# untitled.net
KiCad netlist of a schematic drawn in EAGLE
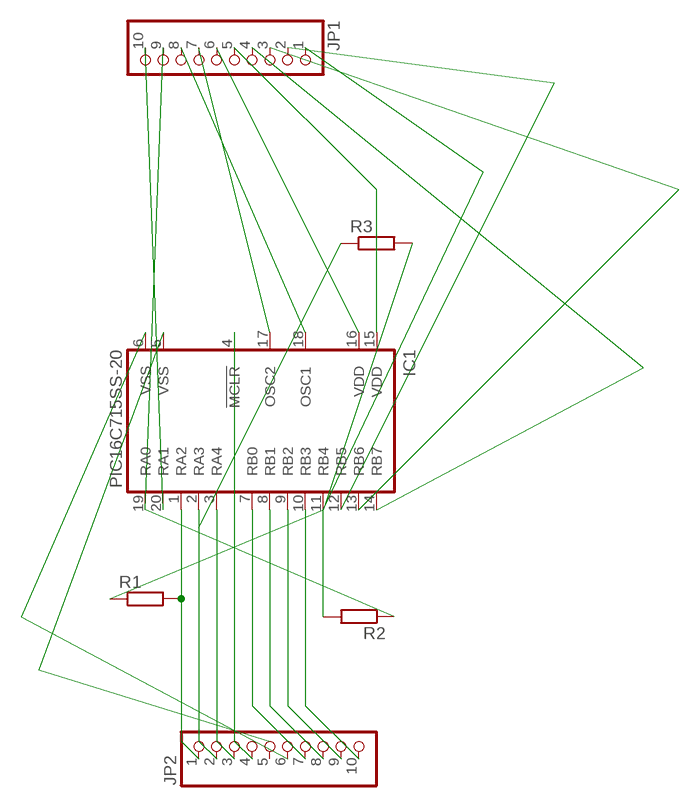
[diagram p0: schematic, sheet 1]

(export (version "E")
  (design (tool "Eeschema 10.0.6"))
  (components
    (comp (ref "IC1")
      (value "PIC16C715SS-20")
      (footprint "eagle-import:SSOP20")
      (fields (field (name "MF") "MICROCHIP") (field (name "MPN") "PIC16C715-04/SS"))
      (libsource (lib "eagle-import") (part "PIC16C?-20SS715"))
    )
    (comp (ref "JP1")
      (value "PINHD-1X10")
      (footprint "eagle-import:1X10")
      (libsource (lib "eagle-import") (part "PINHD-1X10"))
    )
    (comp (ref "JP2")
      (value "PINHD-1X10")
      (footprint "eagle-import:1X10")
      (libsource (lib "eagle-import") (part "PINHD-1X10"))
    )
    (comp (ref "R1")
      (value "R-EU_0207/10")
      (footprint "eagle-import:0207_10")
      (libsource (lib "eagle-import") (part "R-EU_0207/10"))
    )
    (comp (ref "R2")
      (value "R-EU_0204/2V")
      (footprint "eagle-import:0204V")
      (libsource (lib "eagle-import") (part "R-EU_0204/2V"))
    )
    (comp (ref "R3")
      (value "R-EU_0204/2V")
      (footprint "eagle-import:0204V")
      (libsource (lib "eagle-import") (part "R-EU_0204/2V"))
    )
  )
  (nets
    (net (code "1") (name "Net-(IC1-OSC1)") (class "Default")
      (node (ref "IC1") (pin "18") (pinfunction "OSC1_18") (pintype "input"))
      (node (ref "JP1") (pin "8") (pinfunction "8_8") (pintype "passive"))
    )
    (net (code "2") (name "Net-(IC1-OSC2)") (class "Default")
      (node (ref "IC1") (pin "17") (pinfunction "OSC2_17") (pintype "output"))
      (node (ref "JP1") (pin "7") (pinfunction "7_7") (pintype "passive"))
    )
    (net (code "3") (name "Net-(IC1-RA0)") (class "Default")
      (node (ref "IC1") (pin "19") (pinfunction "RA0_19") (pintype "bidirectional"))
      (node (ref "JP1") (pin "9") (pinfunction "9_9") (pintype "passive"))
      (node (ref "R2") (pin "1") (pinfunction "1_1") (pintype "passive"))
    )
    (net (code "4") (name "Net-(IC1-RA1)") (class "Default")
      (node (ref "IC1") (pin "20") (pinfunction "RA1_20") (pintype "bidirectional"))
      (node (ref "JP1") (pin "10") (pinfunction "10_10") (pintype "passive"))
    )
    (net (code "5") (name "Net-(IC1-RA2)") (class "Default")
      (node (ref "IC1") (pin "1") (pinfunction "RA2_1") (pintype "bidirectional"))
      (node (ref "JP2") (pin "1") (pinfunction "1_1") (pintype "passive"))
      (node (ref "R1") (pin "2") (pinfunction "2_2") (pintype "passive"))
    )
    (net (code "6") (name "Net-(IC1-RA3)") (class "Default")
      (node (ref "IC1") (pin "2") (pinfunction "RA3_2") (pintype "bidirectional"))
      (node (ref "JP2") (pin "2") (pinfunction "2_2") (pintype "passive"))
      (node (ref "R3") (pin "1") (pinfunction "1_1") (pintype "passive"))
    )
    (net (code "7") (name "Net-(IC1-RA4)") (class "Default")
      (node (ref "IC1") (pin "3") (pinfunction "RA4_3") (pintype "bidirectional"))
      (node (ref "JP2") (pin "3") (pinfunction "3_3") (pintype "passive"))
    )
    (net (code "8") (name "Net-(IC1-RB0)") (class "Default")
      (node (ref "IC1") (pin "7") (pinfunction "RB0_7") (pintype "bidirectional"))
      (node (ref "JP2") (pin "7") (pinfunction "7_7") (pintype "passive"))
    )
    (net (code "9") (name "Net-(IC1-RB1)") (class "Default")
      (node (ref "IC1") (pin "8") (pinfunction "RB1_8") (pintype "bidirectional"))
      (node (ref "JP2") (pin "8") (pinfunction "8_8") (pintype "passive"))
    )
    (net (code "10") (name "Net-(IC1-RB2)") (class "Default")
      (node (ref "IC1") (pin "9") (pinfunction "RB2_9") (pintype "bidirectional"))
      (node (ref "JP2") (pin "9") (pinfunction "9_9") (pintype "passive"))
    )
    (net (code "11") (name "Net-(IC1-RB3)") (class "Default")
      (node (ref "IC1") (pin "10") (pinfunction "RB3_10") (pintype "bidirectional"))
      (node (ref "JP2") (pin "10") (pinfunction "10_10") (pintype "passive"))
    )
    (net (code "12") (name "Net-(IC1-RB4)") (class "Default")
      (node (ref "IC1") (pin "11") (pinfunction "RB4_11") (pintype "bidirectional"))
      (node (ref "JP1") (pin "1") (pinfunction "1_1") (pintype "passive"))
      (node (ref "R1") (pin "1") (pinfunction "1_1") (pintype "passive"))
      (node (ref "R2") (pin "2") (pinfunction "2_2") (pintype "passive"))
      (node (ref "R3") (pin "2") (pinfunction "2_2") (pintype "passive"))
    )
    (net (code "13") (name "Net-(IC1-RB5)") (class "Default")
      (node (ref "IC1") (pin "12") (pinfunction "RB5_12") (pintype "bidirectional"))
      (node (ref "JP1") (pin "2") (pinfunction "2_2") (pintype "passive"))
    )
    (net (code "14") (name "Net-(IC1-RB6)") (class "Default")
      (node (ref "IC1") (pin "13") (pinfunction "RB6_13") (pintype "bidirectional"))
      (node (ref "JP1") (pin "3") (pinfunction "3_3") (pintype "passive"))
    )
    (net (code "15") (name "Net-(IC1-RB7)") (class "Default")
      (node (ref "IC1") (pin "14") (pinfunction "RB7_14") (pintype "bidirectional"))
      (node (ref "JP1") (pin "4") (pinfunction "4_4") (pintype "passive"))
    )
    (net (code "16") (name "Net-(IC1-VDD-Pad15)") (class "Default")
      (node (ref "IC1") (pin "15") (pinfunction "VDD_15") (pintype "power_in"))
      (node (ref "JP1") (pin "5") (pinfunction "5_5") (pintype "passive"))
    )
    (net (code "17") (name "Net-(IC1-VDD-Pad16)") (class "Default")
      (node (ref "IC1") (pin "16") (pinfunction "VDD_16") (pintype "power_in"))
      (node (ref "JP1") (pin "6") (pinfunction "6_6") (pintype "passive"))
    )
    (net (code "18") (name "Net-(IC1-VSS-Pad6)") (class "Default")
      (node (ref "IC1") (pin "6") (pinfunction "VSS_6") (pintype "power_in"))
      (node (ref "JP2") (pin "6") (pinfunction "6_6") (pintype "passive"))
    )
    (net (code "19") (name "Net-(IC1-~{MCLR})") (class "Default")
      (node (ref "IC1") (pin "4") (pinfunction "~{MCLR}_4") (pintype "input"))
      (node (ref "JP2") (pin "4") (pinfunction "4_4") (pintype "passive"))
    )
    (net (code "20") (name "unconnected-(IC1-VSS-Pad5)") (class "Default")
      (node (ref "IC1") (pin "5") (pinfunction "VSS_5") (pintype "power_in"))
    )
    (net (code "21") (name "unconnected-(JP2-Pad5)") (class "Default")
      (node (ref "JP2") (pin "5") (pinfunction "5_5") (pintype "passive"))
    )
  )
)
